# Electronics_Heater.net
KiCad netlist of a schematic drawn in Altium Designer
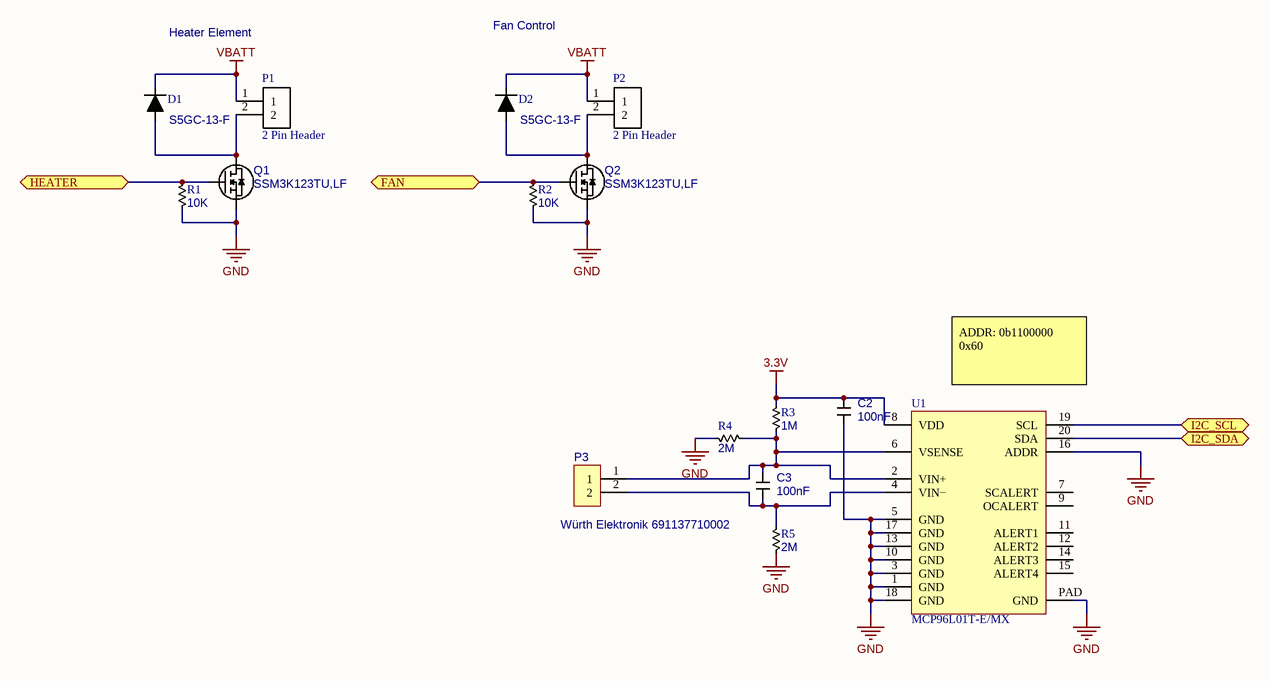
[diagram p0: Electronics Heater.SchDoc]

(export (version "E")
  (design (tool "Eeschema 10.0.6"))
  (components
    (comp (ref "C2")
      (value "100nF")
      (footprint "C0805")
      (description "Capacitor")
      (fields
        (field (name "MANUFACTURER") "YAGEO")
        (field (name "MANUFACTURER PART NUMBER") "CC0805KRX7R9BB104")
      )
      (libsource (lib "Rigby Electronics Schematic Library") (part "Capacitor"))
    )
    (comp (ref "C3")
      (value "100nF")
      (footprint "C0805")
      (description "Capacitor")
      (fields
        (field (name "MANUFACTURER") "YAGEO")
        (field (name "MANUFACTURER PART NUMBER") "CC0805KRX7R9BB104")
      )
      (libsource (lib "Rigby Electronics Schematic Library") (part "Capacitor"))
    )
    (comp (ref "D1")
      (value "S5GC-13-F")
      (footprint "SMC")
      (description "Diode")
      (fields
        (field (name "MANUFACTURER") "Diodes Incorporated")
        (field (name "MANUFACTURER PART NUMBER") "S5GC-13-F")
        (field (name "VOLTAGE") "400V")
      )
      (libsource (lib "Rigby Electronics Schematic Library") (part "Diode"))
    )
    (comp (ref "D2")
      (value "S5GC-13-F")
      (footprint "SMC")
      (description "Diode")
      (fields
        (field (name "MANUFACTURER") "Diodes Incorporated")
        (field (name "MANUFACTURER PART NUMBER") "S5GC-13-F")
        (field (name "VOLTAGE") "400V")
      )
      (libsource (lib "Rigby Electronics Schematic Library") (part "Diode"))
    )
    (comp (ref "P1")
      (value "2 Pin Header")
      (footprint "S2B-XH-A(LF)(SN)")
      (fields
        (field (name "MANUFACTURER") "JST Sales America Inc.")
        (field (name "MANUFACTURER PART NUMBER") "S2B-XH-A")
      )
      (libsource (lib "Rigby Electronics Schematic Library") (part "Header 2"))
    )
    (comp (ref "P2")
      (value "2 Pin Header")
      (footprint "S2B-XH-A(LF)(SN)")
      (fields
        (field (name "MANUFACTURER") "JST Sales America Inc.")
        (field (name "MANUFACTURER PART NUMBER") "S2B-XH-A")
      )
      (libsource (lib "Rigby Electronics Schematic Library") (part "Header 2"))
    )
    (comp (ref "P3")
      (value "Würth Elektronik 691137710002")
      (footprint "Würth Elektronik 691137710002")
      (description "2 Position Wire to Board Terminal Block Horizontal with Board 0.197\" (5.00mm) Through Hole")
      (fields
        (field (name "MANUFACTURER") "Würth Elektronik")
        (field (name "MANUFACTURER PART NUMBER") "691137710002")
      )
      (libsource (lib "Rigby Electronics Schematic Library") (part "Würth Elektronik 691137710002"))
    )
    (comp (ref "Q1")
      (value "SSM3K123TU,LF")
      (footprint "SSM3K123TU,LF")
      (description "N-Channel 20 V 4.2A (Ta) 500mW (Ta) Surface Mount UFM")
      (fields (field (name "MANUFACTURER") "Toshiba Semiconductor and Storage"))
      (libsource (lib "Rigby Electronics Schematic Library") (part "SSM3K123TU,LF"))
    )
    (comp (ref "Q2")
      (value "SSM3K123TU,LF")
      (footprint "SSM3K123TU,LF")
      (description "N-Channel 20 V 4.2A (Ta) 500mW (Ta) Surface Mount UFM")
      (fields (field (name "MANUFACTURER") "Toshiba Semiconductor and Storage"))
      (libsource (lib "Rigby Electronics Schematic Library") (part "SSM3K123TU,LF"))
    )
    (comp (ref "R1")
      (value "330Ω")
      (footprint "R0805")
      (description "Standard Resistor")
      (fields
        (field (name "MANUFACTURER") "YAGEO")
        (field (name "MANUFACTURER PART NUMBER") "RC0805JR-0710KL")
        (field (name "RESISTANCE") "10K")
      )
      (libsource (lib "Rigby Electronics Schematic Library") (part "Resistor"))
    )
    (comp (ref "R2")
      (value "330Ω")
      (footprint "R0805")
      (description "Standard Resistor")
      (fields
        (field (name "MANUFACTURER") "YAGEO")
        (field (name "MANUFACTURER PART NUMBER") "RC0805JR-0710KL")
        (field (name "RESISTANCE") "10K")
      )
      (libsource (lib "Rigby Electronics Schematic Library") (part "Resistor"))
    )
    (comp (ref "R3")
      (value "330Ω")
      (footprint "R0805")
      (description "Standard Resistor")
      (fields
        (field (name "MANUFACTURER") "Panasonic Electronic Components")
        (field (name "MANUFACTURER PART NUMBER") "ERA-6AEB105V")
        (field (name "RESISTANCE") "1M")
      )
      (libsource (lib "Rigby Electronics Schematic Library") (part "Resistor"))
    )
    (comp (ref "R4")
      (value "330Ω")
      (footprint "R0805")
      (description "Standard Resistor")
      (fields
        (field (name "MANUFACTURER") "Vishay Dale")
        (field (name "MANUFACTURER PART NUMBER") "CRCW08052M00FKECC")
        (field (name "RESISTANCE") "2M")
      )
      (libsource (lib "") (part "Resistor_1"))
    )
    (comp (ref "R5")
      (value "330Ω")
      (footprint "R0805")
      (description "Standard Resistor")
      (fields
        (field (name "MANUFACTURER") "Vishay Dale")
        (field (name "MANUFACTURER PART NUMBER") "CRCW08052M00FKECC")
        (field (name "RESISTANCE") "2M")
      )
      (libsource (lib "") (part "Resistor_1"))
    )
    (comp (ref "U1")
      (value "MCP96L01T-E/MX")
      (footprint "MCP96L01T-E/MX")
      (description "Thermocouple EMF to Temperature Converter,  ±1.5°C Maximum Accuracy")
      (fields (field (name "MANUFACTURER") "Microchip Technology"))
      (libsource (lib "Rigby Electronics Schematic Library") (part "MCP96L01T-E/MX"))
    )
  )
  (nets
    (net (code "1") (name "/FAN") (class "Default")
      (node (ref "Q2") (pin "1") (pinfunction "1_1") (pintype "passive"))
      (node (ref "R2") (pin "2") (pinfunction "2_2") (pintype "passive"))
    )
    (net (code "2") (name "/HEATER") (class "Default")
      (node (ref "Q1") (pin "1") (pinfunction "1_1") (pintype "passive"))
      (node (ref "R1") (pin "2") (pinfunction "2_2") (pintype "passive"))
    )
    (net (code "3") (name "/I2C_SCL") (class "Default")
      (node (ref "U1") (pin "19") (pinfunction "SCL_19") (pintype "passive"))
    )
    (net (code "4") (name "/I2C_SDA") (class "Default")
      (node (ref "U1") (pin "20") (pinfunction "SDA_20") (pintype "passive"))
    )
    (net (code "5") (name "3.3V") (class "Default")
      (node (ref "C2") (pin "1") (pinfunction "1_1") (pintype "passive"))
      (node (ref "R3") (pin "2") (pinfunction "2_2") (pintype "passive"))
      (node (ref "U1") (pin "8") (pinfunction "VDD_8") (pintype "passive"))
    )
    (net (code "6") (name "GND") (class "Default")
      (node (ref "C2") (pin "2") (pinfunction "2_2") (pintype "passive"))
      (node (ref "Q1") (pin "2") (pinfunction "2_2") (pintype "passive"))
      (node (ref "Q2") (pin "2") (pinfunction "2_2") (pintype "passive"))
      (node (ref "R1") (pin "1") (pinfunction "1_1") (pintype "passive"))
      (node (ref "R2") (pin "1") (pinfunction "1_1") (pintype "passive"))
      (node (ref "R4") (pin "2") (pinfunction "2_2") (pintype "passive"))
      (node (ref "R5") (pin "2") (pinfunction "2_2") (pintype "passive"))
      (node (ref "U1") (pin "1") (pinfunction "GND_1") (pintype "passive"))
      (node (ref "U1") (pin "10") (pinfunction "GND_10") (pintype "passive"))
      (node (ref "U1") (pin "13") (pinfunction "GND_13") (pintype "passive"))
      (node (ref "U1") (pin "16") (pinfunction "ADDR_16") (pintype "passive"))
      (node (ref "U1") (pin "17") (pinfunction "GND_17") (pintype "passive"))
      (node (ref "U1") (pin "18") (pinfunction "GND_18") (pintype "passive"))
      (node (ref "U1") (pin "3") (pinfunction "GND_3") (pintype "passive"))
      (node (ref "U1") (pin "5") (pinfunction "GND_5") (pintype "passive"))
      (node (ref "U1") (pin "PAD") (pinfunction "GND_PAD") (pintype "passive"))
    )
    (net (code "7") (name "Net-(D1-Pad2)") (class "Default")
      (node (ref "D1") (pin "2") (pinfunction "2_2") (pintype "passive"))
      (node (ref "P1") (pin "2") (pinfunction "2_2") (pintype "passive"))
      (node (ref "Q1") (pin "3") (pinfunction "3_3") (pintype "passive"))
    )
    (net (code "8") (name "Net-(D2-Pad2)") (class "Default")
      (node (ref "D2") (pin "2") (pinfunction "2_2") (pintype "passive"))
      (node (ref "P2") (pin "2") (pinfunction "2_2") (pintype "passive"))
      (node (ref "Q2") (pin "3") (pinfunction "3_3") (pintype "passive"))
    )
    (net (code "9") (name "Net-(U1-VIN+)") (class "Default")
      (node (ref "C3") (pin "1") (pinfunction "1_1") (pintype "passive"))
      (node (ref "P3") (pin "1") (pinfunction "1_1") (pintype "passive"))
      (node (ref "R3") (pin "1") (pinfunction "1_1") (pintype "passive"))
      (node (ref "R4") (pin "1") (pinfunction "1_1") (pintype "passive"))
      (node (ref "U1") (pin "2") (pinfunction "VIN+_2") (pintype "passive"))
      (node (ref "U1") (pin "6") (pinfunction "VSENSE_6") (pintype "passive"))
    )
    (net (code "10") (name "Net-(U1-VIN−)") (class "Default")
      (node (ref "C3") (pin "2") (pinfunction "2_2") (pintype "passive"))
      (node (ref "P3") (pin "2") (pinfunction "2_2") (pintype "passive"))
      (node (ref "R5") (pin "1") (pinfunction "1_1") (pintype "passive"))
      (node (ref "U1") (pin "4") (pinfunction "VIN−_4") (pintype "passive"))
    )
    (net (code "11") (name "VBATT") (class "Default")
      (node (ref "D1") (pin "1") (pinfunction "1_1") (pintype "passive"))
      (node (ref "D2") (pin "1") (pinfunction "1_1") (pintype "passive"))
      (node (ref "P1") (pin "1") (pinfunction "1_1") (pintype "passive"))
      (node (ref "P2") (pin "1") (pinfunction "1_1") (pintype "passive"))
    )
    (net (code "12") (name "unconnected-(U1-ALERT1-Pad11)") (class "Default")
      (node (ref "U1") (pin "11") (pinfunction "ALERT1_11") (pintype "passive"))
    )
    (net (code "13") (name "unconnected-(U1-ALERT2-Pad12)") (class "Default")
      (node (ref "U1") (pin "12") (pinfunction "ALERT2_12") (pintype "passive"))
    )
    (net (code "14") (name "unconnected-(U1-ALERT3-Pad14)") (class "Default")
      (node (ref "U1") (pin "14") (pinfunction "ALERT3_14") (pintype "passive"))
    )
    (net (code "15") (name "unconnected-(U1-ALERT4-Pad15)") (class "Default")
      (node (ref "U1") (pin "15") (pinfunction "ALERT4_15") (pintype "passive"))
    )
    (net (code "16") (name "unconnected-(U1-OCALERT-Pad9)") (class "Default")
      (node (ref "U1") (pin "9") (pinfunction "OCALERT_9") (pintype "passive"))
    )
    (net (code "17") (name "unconnected-(U1-SCALERT-Pad7)") (class "Default")
      (node (ref "U1") (pin "7") (pinfunction "SCALERT_7") (pintype "passive"))
    )
  )
)
